# Sheet1.net
KiCad netlist of a schematic drawn in Altium Designer
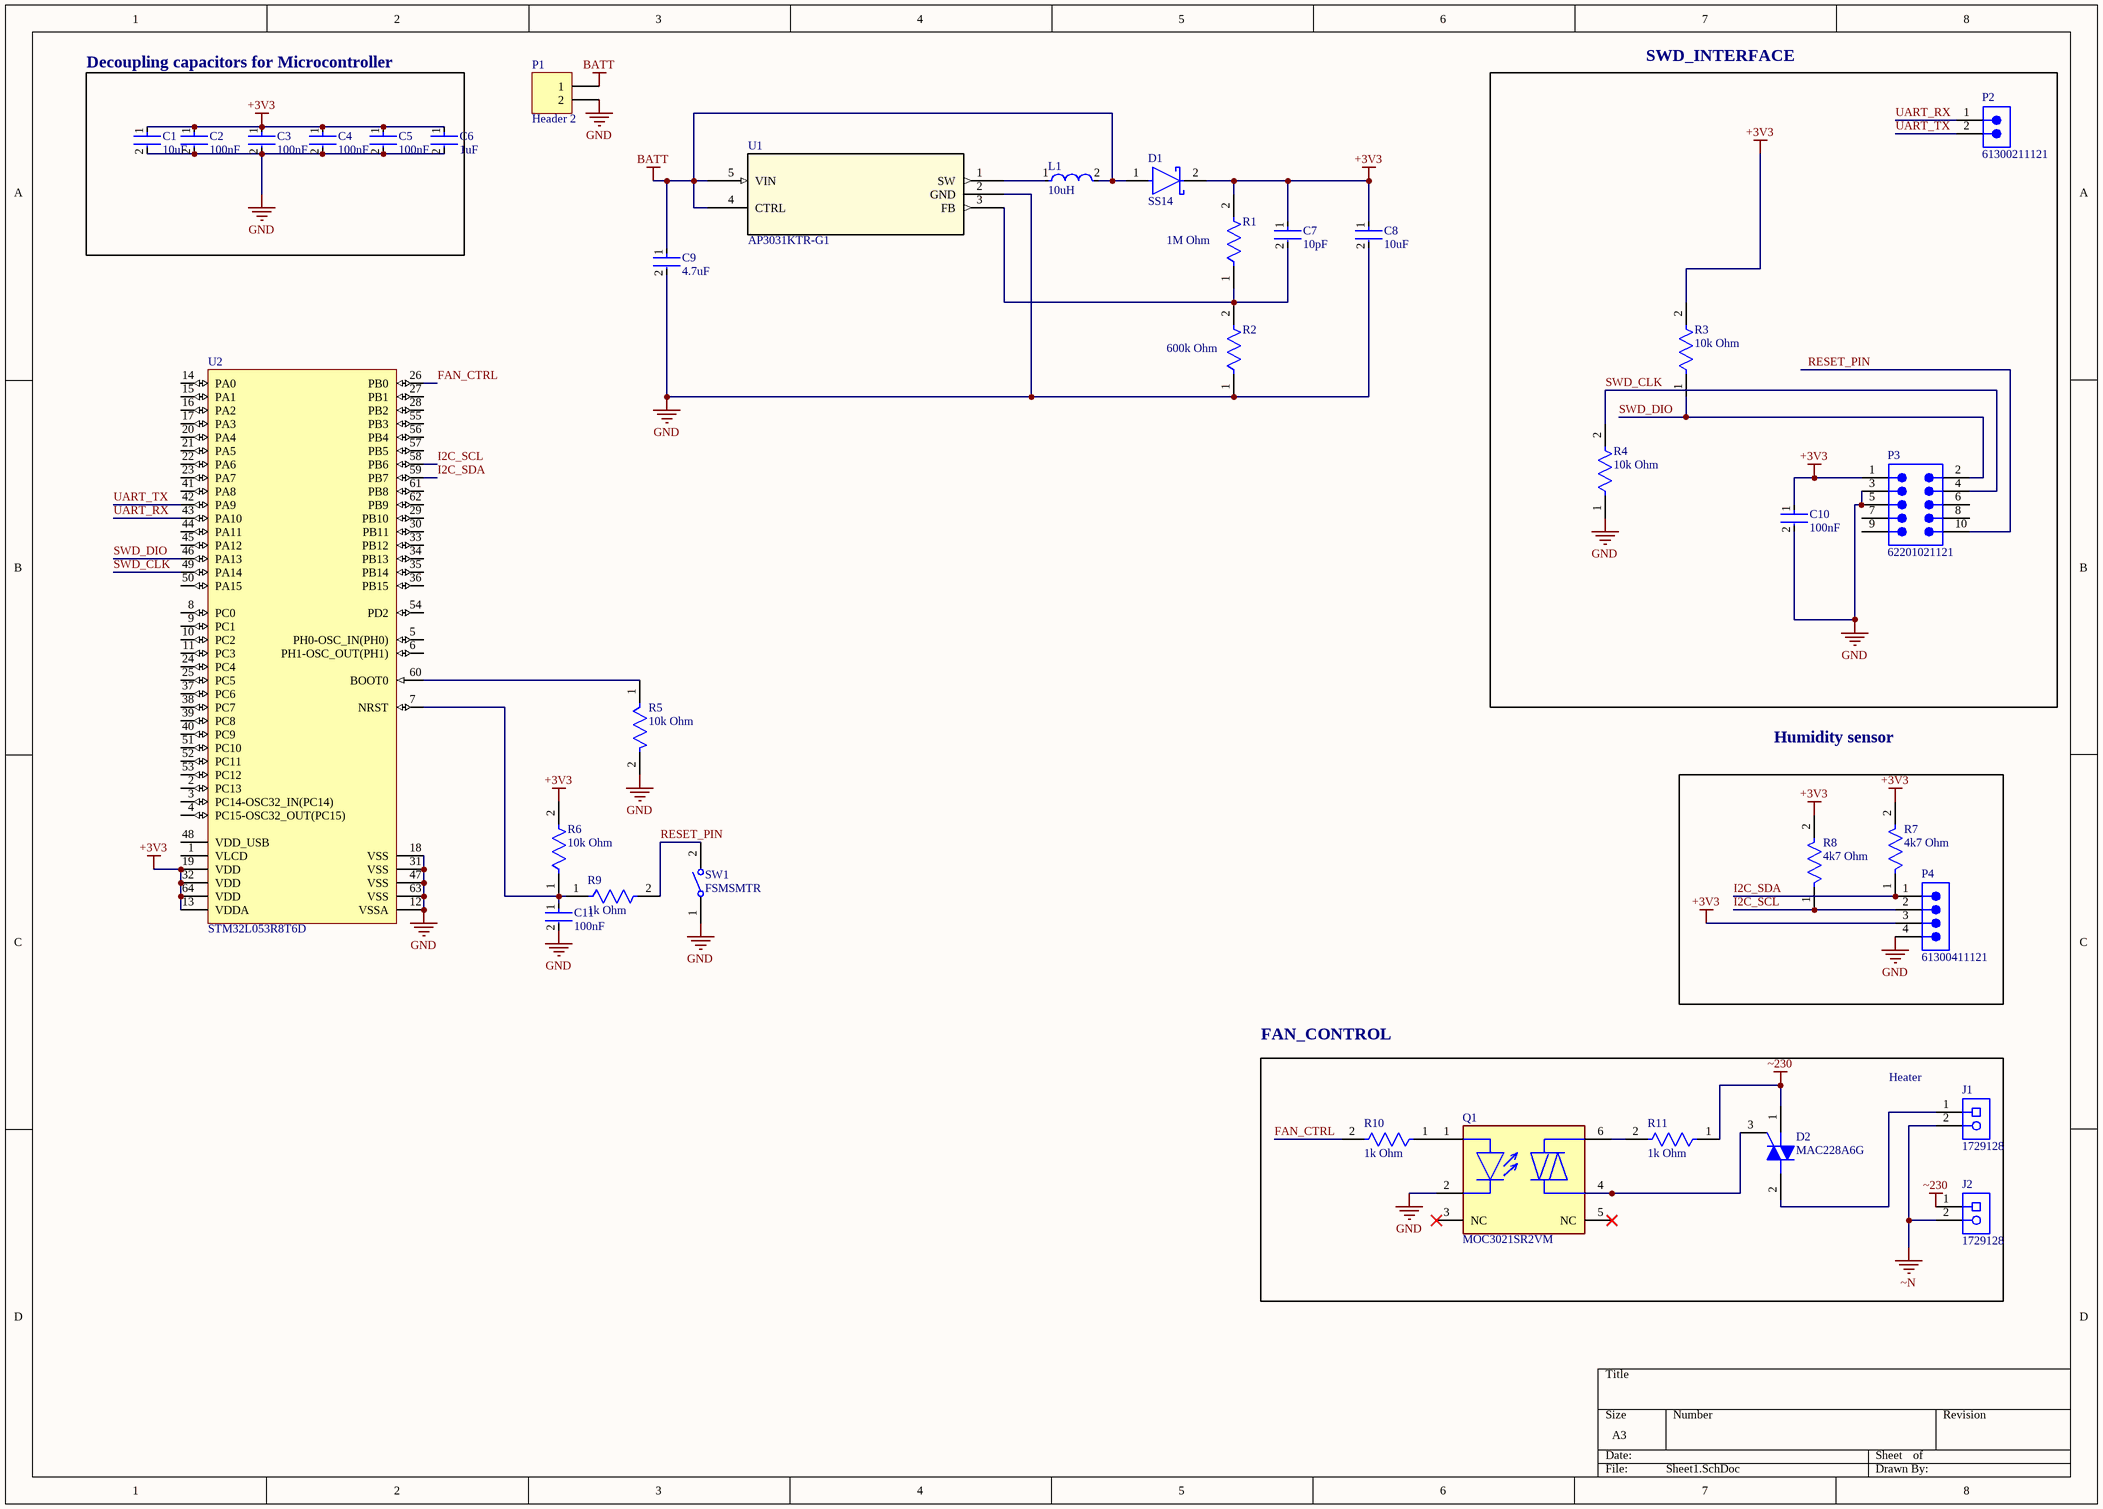
[diagram p0: Sheet1.SchDoc]

(export (version "E")
  (design (tool "Eeschema 10.0.6"))
  (components
    (comp (ref "C1")
      (value "10uF")
      (footprint "FP-CC0805-0_85-MFG")
      (description "CAP CER 0.1UF 50V X7R 0805")
      (fields (field (name "TOLERANCE") "0.1") (field (name "MANUFACTURER PART NUMBER") "CC0805KRX7R9BB104"))
      (libsource (lib "Altium Content Vault") (part "11868f565c42a9108669ba33697ecf6"))
    )
    (comp (ref "C2")
      (value "100nF")
      (footprint "FP-CC0805-0_85-MFG")
      (description "CAP CER 0.1UF 50V X7R 0805")
      (fields (field (name "TOLERANCE") "0.1") (field (name "MANUFACTURER PART NUMBER") "CC0805KRX7R9BB104"))
      (libsource (lib "Altium Content Vault") (part "11868f565c42a9108669ba33697ecf6"))
    )
    (comp (ref "C3")
      (value "100nF")
      (footprint "FP-CC0805-0_85-MFG")
      (description "CAP CER 0.1UF 50V X7R 0805")
      (fields (field (name "TOLERANCE") "0.1") (field (name "MANUFACTURER PART NUMBER") "CC0805KRX7R9BB104"))
      (libsource (lib "Altium Content Vault") (part "11868f565c42a9108669ba33697ecf6"))
    )
    (comp (ref "C4")
      (value "100nF")
      (footprint "FP-CC0805-0_85-MFG")
      (description "CAP CER 0.1UF 50V X7R 0805")
      (fields (field (name "TOLERANCE") "0.1") (field (name "MANUFACTURER PART NUMBER") "CC0805KRX7R9BB104"))
      (libsource (lib "Altium Content Vault") (part "11868f565c42a9108669ba33697ecf6"))
    )
    (comp (ref "C5")
      (value "100nF")
      (footprint "FP-CC0805-0_85-MFG")
      (description "CAP CER 0.1UF 50V X7R 0805")
      (fields (field (name "TOLERANCE") "0.1") (field (name "MANUFACTURER PART NUMBER") "CC0805KRX7R9BB104"))
      (libsource (lib "Altium Content Vault") (part "11868f565c42a9108669ba33697ecf6"))
    )
    (comp (ref "C6")
      (value "1uF")
      (footprint "FP-CC0805-0_85-MFG")
      (description "CAP CER 0.1UF 50V X7R 0805")
      (fields (field (name "TOLERANCE") "0.1") (field (name "MANUFACTURER PART NUMBER") "CC0805KRX7R9BB104"))
      (libsource (lib "Altium Content Vault") (part "11868f565c42a9108669ba33697ecf6"))
    )
    (comp (ref "C7")
      (value "10pF")
      (footprint "FP-CC0805-0_85-MFG")
      (description "CAP CER 0.1UF 50V X7R 0805")
      (fields (field (name "TOLERANCE") "0.1") (field (name "MANUFACTURER PART NUMBER") "CC0805KRX7R9BB104"))
      (libsource (lib "Altium Content Vault") (part "11868f565c42a9108669ba33697ecf6"))
    )
    (comp (ref "C8")
      (value "10uF")
      (footprint "FP-CC0805-0_85-MFG")
      (description "CAP CER 0.1UF 50V X7R 0805")
      (fields (field (name "TOLERANCE") "0.1") (field (name "MANUFACTURER PART NUMBER") "CC0805KRX7R9BB104"))
      (libsource (lib "Altium Content Vault") (part "11868f565c42a9108669ba33697ecf6"))
    )
    (comp (ref "C9")
      (value "4.7uF")
      (footprint "FP-CC0805-0_85-MFG")
      (description "CAP CER 0.1UF 50V X7R 0805")
      (fields (field (name "TOLERANCE") "0.1") (field (name "MANUFACTURER PART NUMBER") "CC0805KRX7R9BB104"))
      (libsource (lib "Altium Content Vault") (part "11868f565c42a9108669ba33697ecf6"))
    )
    (comp (ref "C10")
      (value "100nF")
      (footprint "FP-CC0805-0_85-MFG")
      (description "CAP CER 0.1UF 50V X7R 0805")
      (fields (field (name "TOLERANCE") "0.1") (field (name "MANUFACTURER PART NUMBER") "CC0805KRX7R9BB104"))
      (libsource (lib "Altium Content Vault") (part "11868f565c42a9108669ba33697ecf6"))
    )
    (comp (ref "C11")
      (value "100nF")
      (footprint "FP-CC0805-0_85-MFG")
      (description "CAP CER 0.1UF 50V X7R 0805")
      (fields (field (name "TOLERANCE") "0.1") (field (name "MANUFACTURER PART NUMBER") "CC0805KRX7R9BB104"))
      (libsource (lib "Altium Content Vault") (part "11868f565c42a9108669ba33697ecf6"))
    )
    (comp (ref "D1")
      (value "SS14")
      (footprint "FP-403AE-MFG")
      (description "ON SEMICONDUCTOR - - DIODE, SCHOTTKY, 1A, 40V, DO-214AC-2")
      (fields (field (name "MANUFACTURER") "ON Semiconductor"))
      (libsource (lib "Altium Content Vault") (part "360ad2f4ac25a952324d13796385471"))
    )
    (comp (ref "D2")
      (value "MAC228A6G")
      (footprint "ONSC-TO-220-3-221A-09")
      (description "Sensitive Gate Triacs, Silicon Bidirectional Thyristor, 3-Pin TO-220, Pb-Free, Bulk Box")
      (fields (field (name "MANUFACTURER") "On Semiconductor"))
      (libsource (lib "Altium Content Vault") (part "ONSC-TRIAC-MT1MT2G-3"))
    )
    (comp (ref "J1")
      (value "1729128")
      (footprint "PHOE-1729128-2_V")
      (description "PCB Terminal Block, 13.5 A, 400 V, 2-Pin THD, RoHS, Bulk")
      (fields (field (name "MANUFACTURER") "Phoenix Contact"))
      (libsource (lib "Altium Content Vault") (part "CN-2P-F-R2"))
    )
    (comp (ref "J2")
      (value "1729128")
      (footprint "PHOE-1729128-2_V")
      (description "PCB Terminal Block, 13.5 A, 400 V, 2-Pin THD, RoHS, Bulk")
      (fields (field (name "MANUFACTURER") "Phoenix Contact"))
      (libsource (lib "Altium Content Vault") (part "CN-2P-F-R2"))
    )
    (comp (ref "L1")
      (value "10uH")
      (footprint "FP-LQH43CN_03-MFG")
      (description "Wire Wound Ferrite Inductor for General Circuits 470μH ±10% 11.8Ω 80mA 1812")
      (fields (field (name "TOLERANCE") "10%"))
      (libsource (lib "Altium Content Vault") (part "725321dda6339637d4d059423bc1c3c"))
    )
    (comp (ref "P1")
      (value "Header 2")
      (footprint "HDR1X2")
      (description "Header, 2-Pin")
      (fields (field (name "PUBLISHER") "Altium Limited"))
      (libsource (lib "Miscellaneous Connectors") (part "Header 2"))
    )
    (comp (ref "P2")
      (value "61300211121")
      (footprint "61300211121")
      (libsource (lib "Altium Content Vault") (part "Header_Male_1R_02P"))
    )
    (comp (ref "P3")
      (value "62201021121")
      (footprint "62201021121")
      (libsource (lib "Altium Content Vault") (part "Header_Male_2R_10P"))
    )
    (comp (ref "P4")
      (value "61300411121")
      (footprint "61300411121")
      (libsource (lib "Altium Content Vault") (part "Header_Male_1R_04P"))
    )
    (comp (ref "Q1")
      (value "MOC3021SR2VM")
      (footprint "FP-646BY-MFG")
      (description "MOC3021SR2VM Triac Driver Output Optocoupler, 6-Pin DIP 400V Random Phase")
      (libsource (lib "Altium Content Vault") (part "315d33d7a3de83856d3bd334bf87c2f"))
    )
    (comp (ref "R1")
      (value "1M Ohm")
      (footprint "FP-RMCF0805-MFG")
      (description "RES 0 OHM JUMPER 1/8W 0805")
      (libsource (lib "Altium Content Vault") (part "1029c3af85768c4190bb7ad29bc67b5"))
    )
    (comp (ref "R2")
      (value "600k Ohm")
      (footprint "FP-RMCF0805-MFG")
      (description "RES 0 OHM JUMPER 1/8W 0805")
      (libsource (lib "Altium Content Vault") (part "1029c3af85768c4190bb7ad29bc67b5"))
    )
    (comp (ref "R3")
      (value "10k Ohm")
      (footprint "FP-RMCF0805-MFG")
      (description "RES 0 OHM JUMPER 1/8W 0805")
      (libsource (lib "Altium Content Vault") (part "1029c3af85768c4190bb7ad29bc67b5"))
    )
    (comp (ref "R4")
      (value "10k Ohm")
      (footprint "FP-RMCF0805-MFG")
      (description "RES 0 OHM JUMPER 1/8W 0805")
      (libsource (lib "Altium Content Vault") (part "1029c3af85768c4190bb7ad29bc67b5"))
    )
    (comp (ref "R5")
      (value "10k Ohm")
      (footprint "FP-RMCF0805-MFG")
      (description "RES 0 OHM JUMPER 1/8W 0805")
      (libsource (lib "Altium Content Vault") (part "1029c3af85768c4190bb7ad29bc67b5"))
    )
    (comp (ref "R6")
      (value "10k Ohm")
      (footprint "FP-RMCF0805-MFG")
      (description "RES 0 OHM JUMPER 1/8W 0805")
      (libsource (lib "Altium Content Vault") (part "1029c3af85768c4190bb7ad29bc67b5"))
    )
    (comp (ref "R7")
      (value "4k7 Ohm")
      (footprint "FP-RMCF0805-MFG")
      (description "RES 0 OHM JUMPER 1/8W 0805")
      (libsource (lib "Altium Content Vault") (part "1029c3af85768c4190bb7ad29bc67b5"))
    )
    (comp (ref "R8")
      (value "4k7 Ohm")
      (footprint "FP-RMCF0805-MFG")
      (description "RES 0 OHM JUMPER 1/8W 0805")
      (libsource (lib "Altium Content Vault") (part "1029c3af85768c4190bb7ad29bc67b5"))
    )
    (comp (ref "R9")
      (value "1k Ohm")
      (footprint "FP-RMCF0805-MFG")
      (description "RES 0 OHM JUMPER 1/8W 0805")
      (libsource (lib "Altium Content Vault") (part "1029c3af85768c4190bb7ad29bc67b5"))
    )
    (comp (ref "R10")
      (value "1k Ohm")
      (footprint "FP-RMCF0805-MFG")
      (description "RES 0 OHM JUMPER 1/8W 0805")
      (libsource (lib "Altium Content Vault") (part "1029c3af85768c4190bb7ad29bc67b5"))
    )
    (comp (ref "R11")
      (value "1k Ohm")
      (footprint "FP-RMCF0805-MFG")
      (description "RES 0 OHM JUMPER 1/8W 0805")
      (libsource (lib "Altium Content Vault") (part "1029c3af85768c4190bb7ad29bc67b5"))
    )
    (comp (ref "SW1")
      (value "FSMSMTR")
      (footprint "TECO-FSMSMTR_V")
      (description "FSMSM Push Button Switch, 50 mA, -35 to 85 degC, 2-Pin SMD, RoHS, Tape and Reel")
      (fields (field (name "MANUFACTURER") "TE Connectivity"))
      (libsource (lib "Altium Content Vault") (part "SW-SPST-2_C"))
    )
    (comp (ref "U1")
      (value "AP3031KTR-G1")
      (footprint "SOT23-6_DIO")
      (description "No Description Available")
      (libsource (lib "AP3031KTR-G1") (part "AP3031KTR-G1"))
    )
    (comp (ref "U2")
      (value "STM32L053R8T6D")
      (footprint "STM-LQFP64_L")
      (libsource (lib "Altium Content Vault") (part "MC-ARM-STM32L053-LQFP64"))
    )
  )
  (nets
    (net (code "1") (name "+3V3") (class "Default")
      (node (ref "C1") (pin "1") (pinfunction "1_1") (pintype "passive"))
      (node (ref "C10") (pin "1") (pinfunction "1_1") (pintype "passive"))
      (node (ref "C2") (pin "1") (pinfunction "1_1") (pintype "passive"))
      (node (ref "C3") (pin "1") (pinfunction "1_1") (pintype "passive"))
      (node (ref "C4") (pin "1") (pinfunction "1_1") (pintype "passive"))
      (node (ref "C5") (pin "1") (pinfunction "1_1") (pintype "passive"))
      (node (ref "C6") (pin "1") (pinfunction "1_1") (pintype "passive"))
      (node (ref "C7") (pin "1") (pinfunction "1_1") (pintype "passive"))
      (node (ref "C8") (pin "1") (pinfunction "1_1") (pintype "passive"))
      (node (ref "D1") (pin "2") (pinfunction "C_2") (pintype "passive"))
      (node (ref "P3") (pin "1") (pinfunction "1_1") (pintype "passive"))
      (node (ref "P4") (pin "3") (pinfunction "3_3") (pintype "passive"))
      (node (ref "R1") (pin "2") (pinfunction "2_2") (pintype "passive"))
      (node (ref "R3") (pin "2") (pinfunction "2_2") (pintype "passive"))
      (node (ref "R6") (pin "2") (pinfunction "2_2") (pintype "passive"))
      (node (ref "R7") (pin "2") (pinfunction "2_2") (pintype "passive"))
      (node (ref "R8") (pin "2") (pinfunction "2_2") (pintype "passive"))
      (node (ref "U2") (pin "13") (pinfunction "VDDA_13") (pintype "power_in"))
      (node (ref "U2") (pin "19") (pinfunction "VDD_19") (pintype "power_in"))
      (node (ref "U2") (pin "32") (pinfunction "VDD_32") (pintype "power_in"))
      (node (ref "U2") (pin "64") (pinfunction "VDD_64") (pintype "power_in"))
    )
    (net (code "2") (name "/FAN_CTRL") (class "Default")
      (node (ref "R10") (pin "2") (pinfunction "2_2") (pintype "passive"))
      (node (ref "U2") (pin "26") (pinfunction "PB0_26") (pintype "bidirectional"))
    )
    (net (code "3") (name "/I2C_SCL") (class "Default")
      (node (ref "P4") (pin "2") (pinfunction "2_2") (pintype "passive"))
      (node (ref "R8") (pin "1") (pinfunction "1_1") (pintype "passive"))
      (node (ref "U2") (pin "58") (pinfunction "PB6_58") (pintype "bidirectional"))
    )
    (net (code "4") (name "/I2C_SDA") (class "Default")
      (node (ref "P4") (pin "1") (pinfunction "1_1") (pintype "passive"))
      (node (ref "R7") (pin "1") (pinfunction "1_1") (pintype "passive"))
      (node (ref "U2") (pin "59") (pinfunction "PB7_59") (pintype "bidirectional"))
    )
    (net (code "5") (name "/RESET_PIN") (class "Default")
      (node (ref "P3") (pin "10") (pinfunction "10_10") (pintype "passive"))
      (node (ref "R9") (pin "2") (pinfunction "2_2") (pintype "passive"))
      (node (ref "SW1") (pin "2") (pinfunction "2_2") (pintype "passive"))
    )
    (net (code "6") (name "/SWD_CLK") (class "Default")
      (node (ref "P3") (pin "4") (pinfunction "4_4") (pintype "passive"))
      (node (ref "R4") (pin "2") (pinfunction "2_2") (pintype "passive"))
      (node (ref "U2") (pin "49") (pinfunction "PA14_49") (pintype "bidirectional"))
    )
    (net (code "7") (name "/SWD_DIO") (class "Default")
      (node (ref "P3") (pin "2") (pinfunction "2_2") (pintype "passive"))
      (node (ref "R3") (pin "1") (pinfunction "1_1") (pintype "passive"))
      (node (ref "U2") (pin "46") (pinfunction "PA13_46") (pintype "bidirectional"))
    )
    (net (code "8") (name "/UART_RX") (class "Default")
      (node (ref "P2") (pin "1") (pinfunction "1_1") (pintype "passive"))
      (node (ref "U2") (pin "43") (pinfunction "PA10_43") (pintype "bidirectional"))
    )
    (net (code "9") (name "/UART_TX") (class "Default")
      (node (ref "P2") (pin "2") (pinfunction "2_2") (pintype "passive"))
      (node (ref "U2") (pin "42") (pinfunction "PA9_42") (pintype "bidirectional"))
    )
    (net (code "10") (name "BATT") (class "Default")
      (node (ref "C9") (pin "1") (pinfunction "1_1") (pintype "passive"))
      (node (ref "D1") (pin "1") (pinfunction "A_1") (pintype "passive"))
      (node (ref "L1") (pin "2") (pinfunction "2_2") (pintype "passive"))
      (node (ref "P1") (pin "1") (pinfunction "1_1") (pintype "passive"))
      (node (ref "U1") (pin "4") (pinfunction "CTRL_4") (pintype "passive"))
      (node (ref "U1") (pin "5") (pinfunction "VIN_5") (pintype "input"))
    )
    (net (code "11") (name "GND") (class "Default")
      (node (ref "C1") (pin "2") (pinfunction "2_2") (pintype "passive"))
      (node (ref "C10") (pin "2") (pinfunction "2_2") (pintype "passive"))
      (node (ref "C11") (pin "2") (pinfunction "2_2") (pintype "passive"))
      (node (ref "C2") (pin "2") (pinfunction "2_2") (pintype "passive"))
      (node (ref "C3") (pin "2") (pinfunction "2_2") (pintype "passive"))
      (node (ref "C4") (pin "2") (pinfunction "2_2") (pintype "passive"))
      (node (ref "C5") (pin "2") (pinfunction "2_2") (pintype "passive"))
      (node (ref "C6") (pin "2") (pinfunction "2_2") (pintype "passive"))
      (node (ref "C8") (pin "2") (pinfunction "2_2") (pintype "passive"))
      (node (ref "C9") (pin "2") (pinfunction "2_2") (pintype "passive"))
      (node (ref "P1") (pin "2") (pinfunction "2_2") (pintype "passive"))
      (node (ref "P3") (pin "3") (pinfunction "3_3") (pintype "passive"))
      (node (ref "P3") (pin "5") (pinfunction "5_5") (pintype "passive"))
      (node (ref "P4") (pin "4") (pinfunction "4_4") (pintype "passive"))
      (node (ref "Q1") (pin "2") (pinfunction "C_2") (pintype "passive"))
      (node (ref "R2") (pin "1") (pinfunction "1_1") (pintype "passive"))
      (node (ref "R4") (pin "1") (pinfunction "1_1") (pintype "passive"))
      (node (ref "R5") (pin "2") (pinfunction "2_2") (pintype "passive"))
      (node (ref "SW1") (pin "1") (pinfunction "1_1") (pintype "passive"))
      (node (ref "U1") (pin "2") (pinfunction "GND_2") (pintype "power_in"))
      (node (ref "U2") (pin "12") (pinfunction "VSSA_12") (pintype "power_in"))
      (node (ref "U2") (pin "18") (pinfunction "VSS_18") (pintype "power_in"))
      (node (ref "U2") (pin "31") (pinfunction "VSS_31") (pintype "power_in"))
      (node (ref "U2") (pin "47") (pinfunction "VSS_47") (pintype "power_in"))
      (node (ref "U2") (pin "63") (pinfunction "VSS_63") (pintype "power_in"))
    )
    (net (code "12") (name "Net-(D2-G)") (class "Default")
      (node (ref "D2") (pin "3") (pinfunction "G_3") (pintype "passive"))
      (node (ref "Q1") (pin "4") (pinfunction "1_MAIN_TERM_4") (pintype "passive"))
    )
    (net (code "13") (name "Net-(D2-MT2)") (class "Default")
      (node (ref "D2") (pin "2") (pinfunction "MT2_2") (pintype "passive"))
      (node (ref "J1") (pin "1") (pinfunction "1_1") (pintype "passive"))
    )
    (net (code "14") (name "Net-(Q1-2_MAIN_TERM)") (class "Default")
      (node (ref "Q1") (pin "6") (pinfunction "2_MAIN_TERM_6") (pintype "passive"))
      (node (ref "R11") (pin "2") (pinfunction "2_2") (pintype "passive"))
    )
    (net (code "15") (name "Net-(Q1-A)") (class "Default")
      (node (ref "Q1") (pin "1") (pinfunction "A_1") (pintype "passive"))
      (node (ref "R10") (pin "1") (pinfunction "1_1") (pintype "passive"))
    )
    (net (code "16") (name "Net-(U1-FB)") (class "Default")
      (node (ref "C7") (pin "2") (pinfunction "2_2") (pintype "passive"))
      (node (ref "R1") (pin "1") (pinfunction "1_1") (pintype "passive"))
      (node (ref "R2") (pin "2") (pinfunction "2_2") (pintype "passive"))
      (node (ref "U1") (pin "3") (pinfunction "FB_3") (pintype "output"))
    )
    (net (code "17") (name "Net-(U1-SW)") (class "Default")
      (node (ref "L1") (pin "1") (pinfunction "1_1") (pintype "passive"))
      (node (ref "U1") (pin "1") (pinfunction "SW_1") (pintype "output"))
    )
    (net (code "18") (name "Net-(U2-BOOT0)") (class "Default")
      (node (ref "R5") (pin "1") (pinfunction "1_1") (pintype "passive"))
      (node (ref "U2") (pin "60") (pinfunction "BOOT0_60") (pintype "input"))
    )
    (net (code "19") (name "Net-(U2-NRST)") (class "Default")
      (node (ref "C11") (pin "1") (pinfunction "1_1") (pintype "passive"))
      (node (ref "R6") (pin "1") (pinfunction "1_1") (pintype "passive"))
      (node (ref "R9") (pin "1") (pinfunction "1_1") (pintype "passive"))
      (node (ref "U2") (pin "7") (pinfunction "NRST_7") (pintype "bidirectional"))
    )
    (net (code "20") (name "unconnected-(P3-Pad6)") (class "Default")
      (node (ref "P3") (pin "6") (pinfunction "6_6") (pintype "passive"))
    )
    (net (code "21") (name "unconnected-(P3-Pad7)") (class "Default")
      (node (ref "P3") (pin "7") (pinfunction "7_7") (pintype "passive"))
    )
    (net (code "22") (name "unconnected-(P3-Pad8)") (class "Default")
      (node (ref "P3") (pin "8") (pinfunction "8_8") (pintype "passive"))
    )
    (net (code "23") (name "unconnected-(P3-Pad9)") (class "Default")
      (node (ref "P3") (pin "9") (pinfunction "9_9") (pintype "passive"))
    )
    (net (code "24") (name "unconnected-(Q1-NC-Pad3)") (class "Default")
      (node (ref "Q1") (pin "3") (pinfunction "NC_3") (pintype "passive+no_connect"))
    )
    (net (code "25") (name "unconnected-(Q1-NC-Pad5)") (class "Default")
      (node (ref "Q1") (pin "5") (pinfunction "NC_5") (pintype "passive+no_connect"))
    )
    (net (code "26") (name "unconnected-(U2-PA0-Pad14)") (class "Default")
      (node (ref "U2") (pin "14") (pinfunction "PA0_14") (pintype "bidirectional"))
    )
    (net (code "27") (name "unconnected-(U2-PA1-Pad15)") (class "Default")
      (node (ref "U2") (pin "15") (pinfunction "PA1_15") (pintype "bidirectional"))
    )
    (net (code "28") (name "unconnected-(U2-PA2-Pad16)") (class "Default")
      (node (ref "U2") (pin "16") (pinfunction "PA2_16") (pintype "bidirectional"))
    )
    (net (code "29") (name "unconnected-(U2-PA3-Pad17)") (class "Default")
      (node (ref "U2") (pin "17") (pinfunction "PA3_17") (pintype "bidirectional"))
    )
    (net (code "30") (name "unconnected-(U2-PA4-Pad20)") (class "Default")
      (node (ref "U2") (pin "20") (pinfunction "PA4_20") (pintype "bidirectional"))
    )
    (net (code "31") (name "unconnected-(U2-PA5-Pad21)") (class "Default")
      (node (ref "U2") (pin "21") (pinfunction "PA5_21") (pintype "bidirectional"))
    )
    (net (code "32") (name "unconnected-(U2-PA6-Pad22)") (class "Default")
      (node (ref "U2") (pin "22") (pinfunction "PA6_22") (pintype "bidirectional"))
    )
    (net (code "33") (name "unconnected-(U2-PA7-Pad23)") (class "Default")
      (node (ref "U2") (pin "23") (pinfunction "PA7_23") (pintype "bidirectional"))
    )
    (net (code "34") (name "unconnected-(U2-PA8-Pad41)") (class "Default")
      (node (ref "U2") (pin "41") (pinfunction "PA8_41") (pintype "bidirectional"))
    )
    (net (code "35") (name "unconnected-(U2-PA11-Pad44)") (class "Default")
      (node (ref "U2") (pin "44") (pinfunction "PA11_44") (pintype "bidirectional"))
    )
    (net (code "36") (name "unconnected-(U2-PA12-Pad45)") (class "Default")
      (node (ref "U2") (pin "45") (pinfunction "PA12_45") (pintype "bidirectional"))
    )
    (net (code "37") (name "unconnected-(U2-PA15-Pad50)") (class "Default")
      (node (ref "U2") (pin "50") (pinfunction "PA15_50") (pintype "bidirectional"))
    )
    (net (code "38") (name "unconnected-(U2-PB1-Pad27)") (class "Default")
      (node (ref "U2") (pin "27") (pinfunction "PB1_27") (pintype "bidirectional"))
    )
    (net (code "39") (name "unconnected-(U2-PB2-Pad28)") (class "Default")
      (node (ref "U2") (pin "28") (pinfunction "PB2_28") (pintype "bidirectional"))
    )
    (net (code "40") (name "unconnected-(U2-PB3-Pad55)") (class "Default")
      (node (ref "U2") (pin "55") (pinfunction "PB3_55") (pintype "bidirectional"))
    )
    (net (code "41") (name "unconnected-(U2-PB4-Pad56)") (class "Default")
      (node (ref "U2") (pin "56") (pinfunction "PB4_56") (pintype "bidirectional"))
    )
    (net (code "42") (name "unconnected-(U2-PB5-Pad57)") (class "Default")
      (node (ref "U2") (pin "57") (pinfunction "PB5_57") (pintype "bidirectional"))
    )
    (net (code "43") (name "unconnected-(U2-PB8-Pad61)") (class "Default")
      (node (ref "U2") (pin "61") (pinfunction "PB8_61") (pintype "bidirectional"))
    )
    (net (code "44") (name "unconnected-(U2-PB9-Pad62)") (class "Default")
      (node (ref "U2") (pin "62") (pinfunction "PB9_62") (pintype "bidirectional"))
    )
    (net (code "45") (name "unconnected-(U2-PB10-Pad29)") (class "Default")
      (node (ref "U2") (pin "29") (pinfunction "PB10_29") (pintype "bidirectional"))
    )
    (net (code "46") (name "unconnected-(U2-PB11-Pad30)") (class "Default")
      (node (ref "U2") (pin "30") (pinfunction "PB11_30") (pintype "bidirectional"))
    )
    (net (code "47") (name "unconnected-(U2-PB12-Pad33)") (class "Default")
      (node (ref "U2") (pin "33") (pinfunction "PB12_33") (pintype "bidirectional"))
    )
    (net (code "48") (name "unconnected-(U2-PB13-Pad34)") (class "Default")
      (node (ref "U2") (pin "34") (pinfunction "PB13_34") (pintype "bidirectional"))
    )
    (net (code "49") (name "unconnected-(U2-PB14-Pad35)") (class "Default")
      (node (ref "U2") (pin "35") (pinfunction "PB14_35") (pintype "bidirectional"))
    )
    (net (code "50") (name "unconnected-(U2-PB15-Pad36)") (class "Default")
      (node (ref "U2") (pin "36") (pinfunction "PB15_36") (pintype "bidirectional"))
    )
    (net (code "51") (name "unconnected-(U2-PC0-Pad8)") (class "Default")
      (node (ref "U2") (pin "8") (pinfunction "PC0_8") (pintype "bidirectional"))
    )
    (net (code "52") (name "unconnected-(U2-PC1-Pad9)") (class "Default")
      (node (ref "U2") (pin "9") (pinfunction "PC1_9") (pintype "bidirectional"))
    )
    (net (code "53") (name "unconnected-(U2-PC2-Pad10)") (class "Default")
      (node (ref "U2") (pin "10") (pinfunction "PC2_10") (pintype "bidirectional"))
    )
    (net (code "54") (name "unconnected-(U2-PC3-Pad11)") (class "Default")
      (node (ref "U2") (pin "11") (pinfunction "PC3_11") (pintype "bidirectional"))
    )
    (net (code "55") (name "unconnected-(U2-PC4-Pad24)") (class "Default")
      (node (ref "U2") (pin "24") (pinfunction "PC4_24") (pintype "bidirectional"))
    )
    (net (code "56") (name "unconnected-(U2-PC5-Pad25)") (class "Default")
      (node (ref "U2") (pin "25") (pinfunction "PC5_25") (pintype "bidirectional"))
    )
    (net (code "57") (name "unconnected-(U2-PC6-Pad37)") (class "Default")
      (node (ref "U2") (pin "37") (pinfunction "PC6_37") (pintype "bidirectional"))
    )
    (net (code "58") (name "unconnected-(U2-PC7-Pad38)") (class "Default")
      (node (ref "U2") (pin "38") (pinfunction "PC7_38") (pintype "bidirectional"))
    )
    (net (code "59") (name "unconnected-(U2-PC8-Pad39)") (class "Default")
      (node (ref "U2") (pin "39") (pinfunction "PC8_39") (pintype "bidirectional"))
    )
    (net (code "60") (name "unconnected-(U2-PC9-Pad40)") (class "Default")
      (node (ref "U2") (pin "40") (pinfunction "PC9_40") (pintype "bidirectional"))
    )
    (net (code "61") (name "unconnected-(U2-PC10-Pad51)") (class "Default")
      (node (ref "U2") (pin "51") (pinfunction "PC10_51") (pintype "bidirectional"))
    )
    (net (code "62") (name "unconnected-(U2-PC11-Pad52)") (class "Default")
      (node (ref "U2") (pin "52") (pinfunction "PC11_52") (pintype "bidirectional"))
    )
    (net (code "63") (name "unconnected-(U2-PC12-Pad53)") (class "Default")
      (node (ref "U2") (pin "53") (pinfunction "PC12_53") (pintype "bidirectional"))
    )
    (net (code "64") (name "unconnected-(U2-PC13-Pad2)") (class "Default")
      (node (ref "U2") (pin "2") (pinfunction "PC13_2") (pintype "bidirectional"))
    )
    (net (code "65") (name "unconnected-(U2-PC14-OSC32_IN(PC14)-Pad3)") (class "Default")
      (node (ref "U2") (pin "3") (pinfunction "PC14-OSC32_IN(PC14)_3") (pintype "bidirectional"))
    )
    (net (code "66") (name "unconnected-(U2-PC15-OSC32_OUT(PC15)-Pad4)") (class "Default")
      (node (ref "U2") (pin "4") (pinfunction "PC15-OSC32_OUT(PC15)_4") (pintype "bidirectional"))
    )
    (net (code "67") (name "unconnected-(U2-PD2-Pad54)") (class "Default")
      (node (ref "U2") (pin "54") (pinfunction "PD2_54") (pintype "bidirectional"))
    )
    (net (code "68") (name "unconnected-(U2-PH0-OSC_IN(PH0)-Pad5)") (class "Default")
      (node (ref "U2") (pin "5") (pinfunction "PH0-OSC_IN(PH0)_5") (pintype "bidirectional"))
    )
    (net (code "69") (name "unconnected-(U2-PH1-OSC_OUT(PH1)-Pad6)") (class "Default")
      (node (ref "U2") (pin "6") (pinfunction "PH1-OSC_OUT(PH1)_6") (pintype "bidirectional"))
    )
    (net (code "70") (name "unconnected-(U2-VDD_USB-Pad48)") (class "Default")
      (node (ref "U2") (pin "48") (pinfunction "VDD_USB_48") (pintype "power_in"))
    )
    (net (code "71") (name "unconnected-(U2-VLCD-Pad1)") (class "Default")
      (node (ref "U2") (pin "1") (pinfunction "VLCD_1") (pintype "power_in"))
    )
    (net (code "72") (name "~230") (class "Default")
      (node (ref "D2") (pin "1") (pinfunction "MT1_1") (pintype "passive"))
      (node (ref "J2") (pin "1") (pinfunction "1_1") (pintype "passive"))
      (node (ref "R11") (pin "1") (pinfunction "1_1") (pintype "passive"))
    )
    (net (code "73") (name "~N") (class "Default")
      (node (ref "J1") (pin "2") (pinfunction "2_2") (pintype "passive"))
      (node (ref "J2") (pin "2") (pinfunction "2_2") (pintype "passive"))
    )
  )
)
